# 5_Power_ports_DXL_Battery.net
KiCad netlist of a schematic drawn in Altium Designer
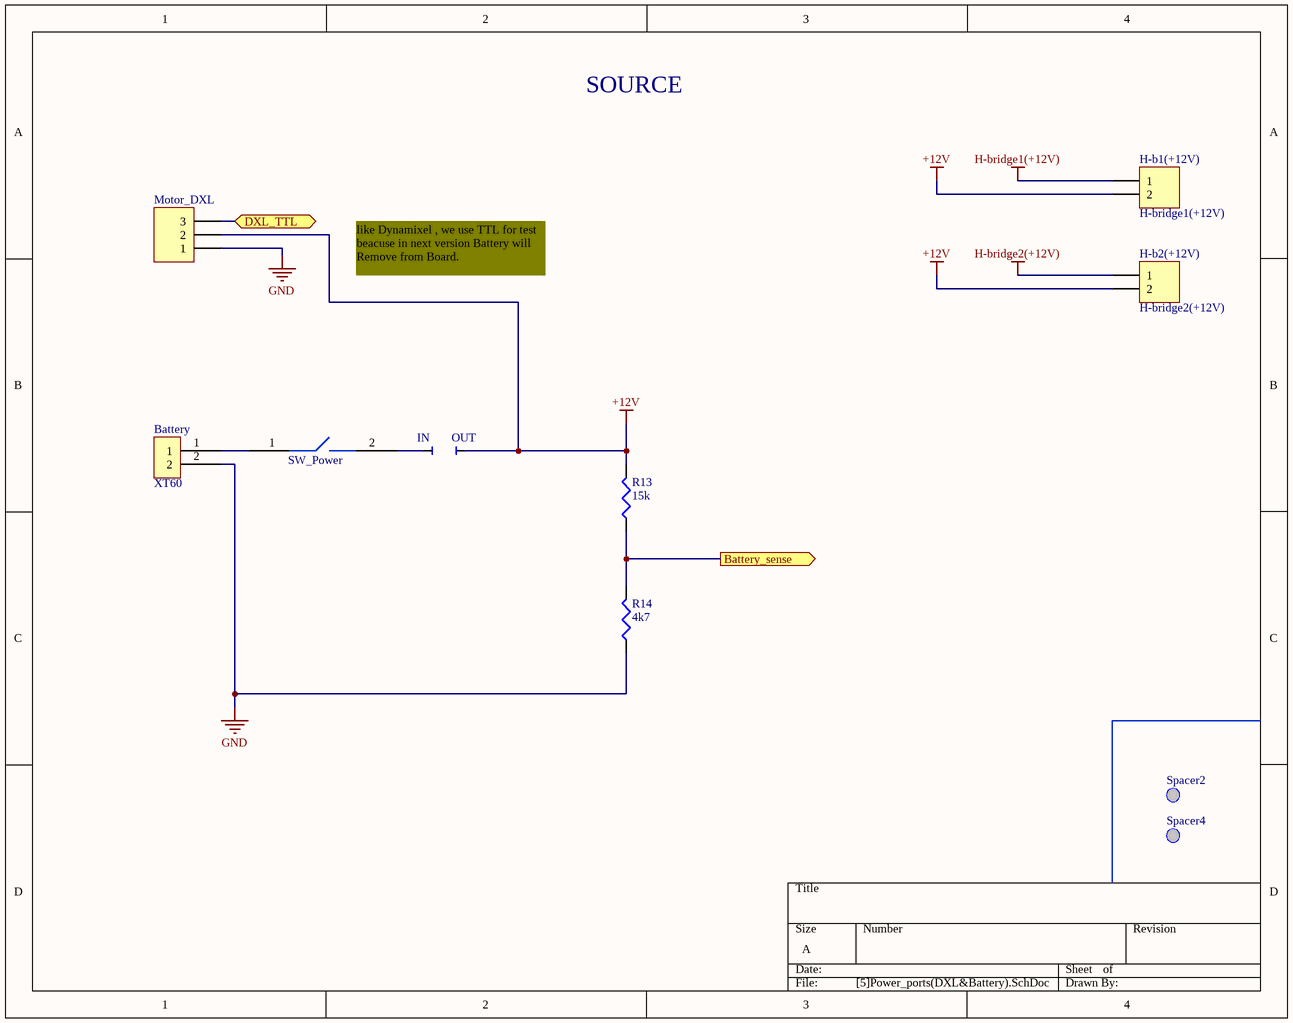
[diagram p0: [5]Power_ports(DXL&Battery).SchDoc]

(export (version "E")
  (design (tool "Eeschema 10.0.6"))
  (components
    (comp (ref "Battery") (value "XT60") (footprint "XT60") (libsource (lib "CM") (part "XT60")))
    (comp (ref "H-b1(+12V)")
      (value "H-bridge1(+12V)")
      (footprint "HDR1X2")
      (description "Header, 2-Pin")
      (fields (field (name "PUBLISHER") "Altium Limited"))
      (libsource (lib "Driver") (part "Header 2"))
    )
    (comp (ref "H-b2(+12V)")
      (value "H-bridge2(+12V)")
      (footprint "HDR1X2")
      (description "Header, 2-Pin")
      (fields (field (name "PUBLISHER") "Altium Limited"))
      (libsource (lib "Driver") (part "Header 2"))
    )
    (comp (ref "IN")
      (value "Fuse Clip")
      (footprint "FUSH_LITTELFUSE_520")
      (fields
        (field (name "PART NUMBER") "FUSH_LITTELFUSE_52000001009")
        (field (name "MANUFACTURER") "LITTELFUSE")
        (field (name "MANUFACTURER PART NUMBER") "52000001009")
        (field (name "AUTHOR") "CERN DEM JLC")
      )
      (libsource (lib "Driver") (part "FUSH_LITTELFUSE_52000001009"))
    )
    (comp (ref "Motor_DXL")
      (value "Molex 22-03-5035")
      (footprint "Molex 22-3-5035")
      (libsource (lib "CM") (part "Molex 22-03-5035"))
    )
    (comp (ref "OUT")
      (value "Fuse Clip")
      (footprint "FUSH_LITTELFUSE_520")
      (fields
        (field (name "PART NUMBER") "FUSH_LITTELFUSE_52000001009")
        (field (name "MANUFACTURER") "LITTELFUSE")
        (field (name "MANUFACTURER PART NUMBER") "52000001009")
        (field (name "AUTHOR") "CERN DEM JLC")
      )
      (libsource (lib "Driver") (part "FUSH_LITTELFUSE_52000001009"))
    )
    (comp (ref "R13") (value "15k") (footprint "Res805") (libsource (lib "CM") (part "Res805")))
    (comp (ref "R14") (value "4k7") (footprint "Res805") (libsource (lib "CM") (part "Res805")))
    (comp (ref "Spacer2")
      (value "Spacer 12mm")
      (footprint "Spacer 12mm")
      (libsource (lib "Spacer 12mm") (part "Spacer 12mm"))
    )
    (comp (ref "Spacer4")
      (value "Spacer 12mm")
      (footprint "Spacer 12mm")
      (libsource (lib "Spacer 12mm") (part "Spacer 12mm"))
    )
    (comp (ref "SW_Power")
      (value "SW_KCD11")
      (footprint "SW_KCD11")
      (description "KCD11")
      (libsource (lib "KCD11") (part "SW_KCD11"))
    )
  )
  (nets
    (net (code "1") (name "+12V") (class "Default")
      (node (ref "H-b1(+12V)") (pin "2") (pinfunction "2_2") (pintype "passive"))
      (node (ref "H-b2(+12V)") (pin "2") (pinfunction "2_2") (pintype "passive"))
      (node (ref "Motor_DXL") (pin "2") (pinfunction "2_2") (pintype "passive"))
      (node (ref "OUT") (pin "1") (pinfunction "1_1") (pintype "passive"))
      (node (ref "R13") (pin "2") (pinfunction "2_2") (pintype "passive"))
    )
    (net (code "2") (name "/Battery_sense") (class "Default")
      (node (ref "R13") (pin "1") (pinfunction "1_1") (pintype "passive"))
      (node (ref "R14") (pin "2") (pinfunction "2_2") (pintype "passive"))
    )
    (net (code "3") (name "/DXL_TTL") (class "Default")
      (node (ref "Motor_DXL") (pin "3") (pinfunction "3_3") (pintype "passive"))
    )
    (net (code "4") (name "GND") (class "Default")
      (node (ref "Battery") (pin "2") (pinfunction "2_2") (pintype "passive"))
      (node (ref "Motor_DXL") (pin "1") (pinfunction "1_1") (pintype "passive"))
      (node (ref "R14") (pin "1") (pinfunction "1_1") (pintype "passive"))
    )
    (net (code "5") (name "H-bridge1(+12V)") (class "Default")
      (node (ref "H-b1(+12V)") (pin "1") (pinfunction "1_1") (pintype "passive"))
    )
    (net (code "6") (name "H-bridge2(+12V)") (class "Default")
      (node (ref "H-b2(+12V)") (pin "1") (pinfunction "1_1") (pintype "passive"))
    )
    (net (code "7") (name "Net-(Battery-Pad1)") (class "Default")
      (node (ref "Battery") (pin "1") (pinfunction "1_1") (pintype "passive"))
      (node (ref "SW_Power") (pin "1") (pinfunction "1_1") (pintype "passive"))
    )
    (net (code "8") (name "Net-(IN-Pad1)") (class "Default")
      (node (ref "IN") (pin "1") (pinfunction "1_1") (pintype "passive"))
      (node (ref "SW_Power") (pin "2") (pinfunction "2_2") (pintype "passive"))
    )
  )
)
